# Power.net
KiCad netlist of a schematic drawn in Altium Designer
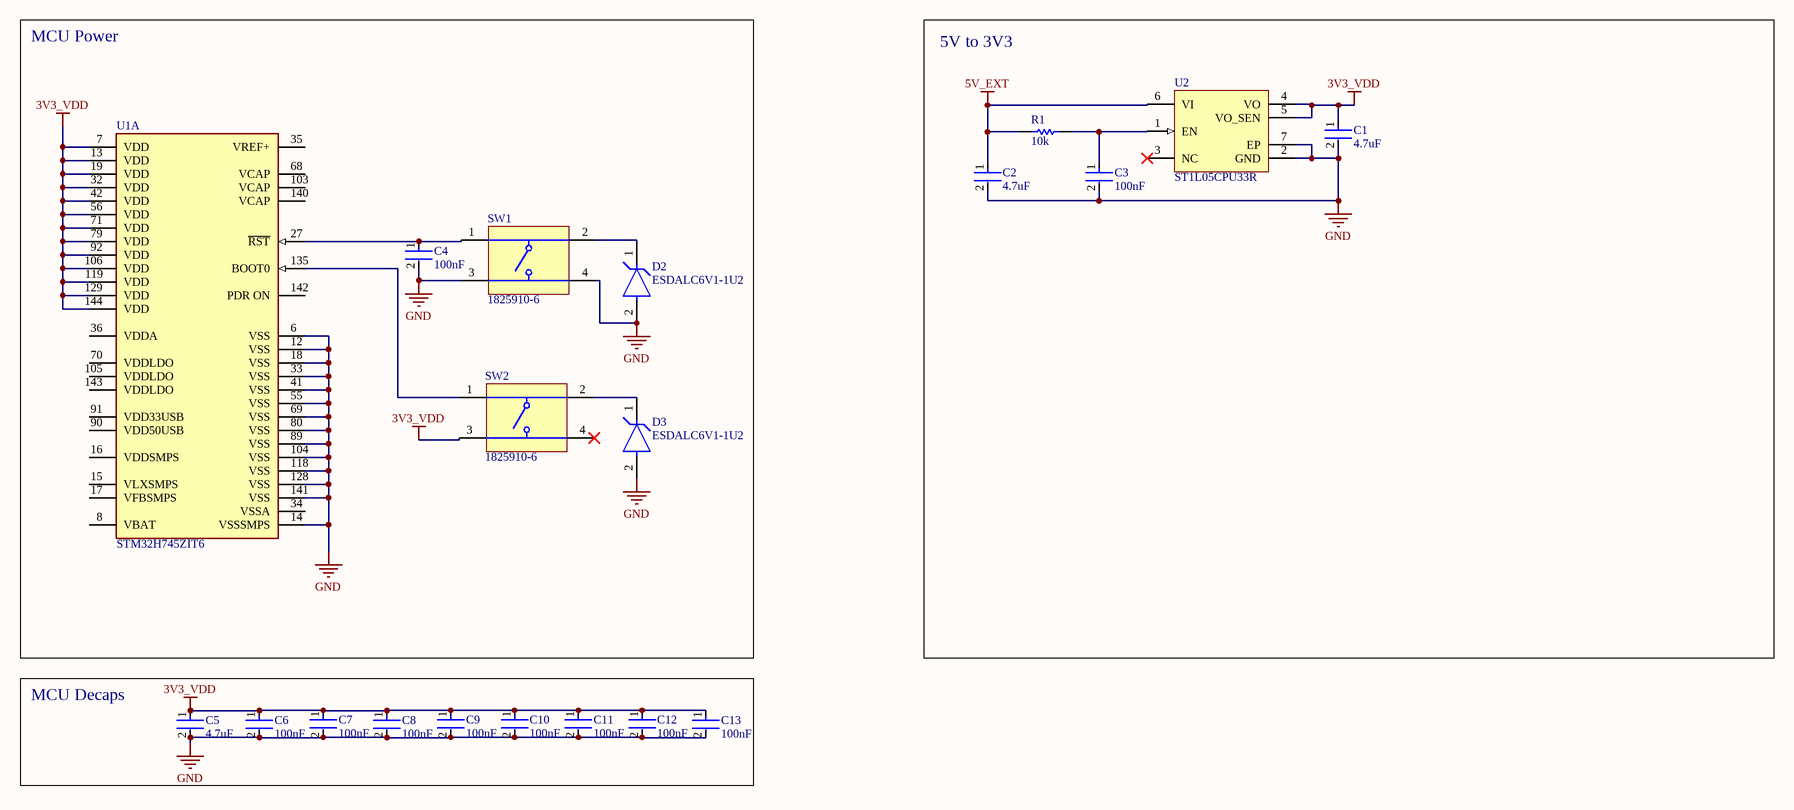
[diagram p0: Power.SchDoc]

(export (version "E")
  (design (tool "Eeschema 10.0.6"))
  (components
    (comp (ref "C1")
      (value "4.7uF")
      (footprint "FP-C0603-CG-MFG")
      (description "CAP CER 4.7UF 6.3V X5R 0603")
      (fields (field (name "TOLERANCE") "10%") (field (name "MANUFACTURER") "Kemet"))
      (libsource (lib "Altium Content Vault") (part "11868f565c42a9108669ba33697ecf6"))
    )
    (comp (ref "C2")
      (value "4.7uF")
      (footprint "FP-C0603-CG-MFG")
      (description "CAP CER 4.7UF 6.3V X5R 0603")
      (fields (field (name "TOLERANCE") "10%") (field (name "MANUFACTURER") "Kemet"))
      (libsource (lib "Altium Content Vault") (part "11868f565c42a9108669ba33697ecf6"))
    )
    (comp (ref "C3")
      (value "100nF")
      (footprint "FP-CGA3E-0_3-0_1-IPC_A")
      (description "Cap Ceramic 100nF 50V X7R 10% Pad SMD 0603 +125°C Automotive T/R")
      (fields (field (name "TOLERANCE") "10%") (field (name "VOLTAGE") "50V"))
      (libsource (lib "Altium Content Vault") (part "b4654b650e69147ec39a6b967a45e02"))
    )
    (comp (ref "C4")
      (value "100nF")
      (footprint "FP-CGA3E-0_3-0_1-IPC_A")
      (description "Cap Ceramic 100nF 50V X7R 10% Pad SMD 0603 +125°C Automotive T/R")
      (fields (field (name "TOLERANCE") "10%") (field (name "VOLTAGE") "50V"))
      (libsource (lib "Altium Content Vault") (part "b4654b650e69147ec39a6b967a45e02"))
    )
    (comp (ref "C5")
      (value "4.7uF")
      (footprint "FP-C0603-CG-MFG")
      (description "CAP CER 4.7UF 6.3V X5R 0603")
      (fields (field (name "TOLERANCE") "10%") (field (name "MANUFACTURER") "Kemet"))
      (libsource (lib "Altium Content Vault") (part "11868f565c42a9108669ba33697ecf6"))
    )
    (comp (ref "C6")
      (value "100nF")
      (footprint "FP-CGA3E-0_3-0_1-IPC_A")
      (description "Cap Ceramic 100nF 50V X7R 10% Pad SMD 0603 +125°C Automotive T/R")
      (fields (field (name "TOLERANCE") "10%") (field (name "VOLTAGE") "50V"))
      (libsource (lib "Altium Content Vault") (part "b4654b650e69147ec39a6b967a45e02"))
    )
    (comp (ref "C7")
      (value "100nF")
      (footprint "FP-CGA3E-0_3-0_1-IPC_A")
      (description "Cap Ceramic 100nF 50V X7R 10% Pad SMD 0603 +125°C Automotive T/R")
      (fields (field (name "TOLERANCE") "10%") (field (name "VOLTAGE") "50V"))
      (libsource (lib "Altium Content Vault") (part "b4654b650e69147ec39a6b967a45e02"))
    )
    (comp (ref "C8")
      (value "100nF")
      (footprint "FP-CGA3E-0_3-0_1-IPC_A")
      (description "Cap Ceramic 100nF 50V X7R 10% Pad SMD 0603 +125°C Automotive T/R")
      (fields (field (name "TOLERANCE") "10%") (field (name "VOLTAGE") "50V"))
      (libsource (lib "Altium Content Vault") (part "b4654b650e69147ec39a6b967a45e02"))
    )
    (comp (ref "C9")
      (value "100nF")
      (footprint "FP-CGA3E-0_3-0_1-IPC_A")
      (description "Cap Ceramic 100nF 50V X7R 10% Pad SMD 0603 +125°C Automotive T/R")
      (fields (field (name "TOLERANCE") "10%") (field (name "VOLTAGE") "50V"))
      (libsource (lib "Altium Content Vault") (part "b4654b650e69147ec39a6b967a45e02"))
    )
    (comp (ref "C10")
      (value "100nF")
      (footprint "FP-CGA3E-0_3-0_1-IPC_A")
      (description "Cap Ceramic 100nF 50V X7R 10% Pad SMD 0603 +125°C Automotive T/R")
      (fields (field (name "TOLERANCE") "10%") (field (name "VOLTAGE") "50V"))
      (libsource (lib "Altium Content Vault") (part "b4654b650e69147ec39a6b967a45e02"))
    )
    (comp (ref "C11")
      (value "100nF")
      (footprint "FP-CGA3E-0_3-0_1-IPC_A")
      (description "Cap Ceramic 100nF 50V X7R 10% Pad SMD 0603 +125°C Automotive T/R")
      (fields (field (name "TOLERANCE") "10%") (field (name "VOLTAGE") "50V"))
      (libsource (lib "Altium Content Vault") (part "b4654b650e69147ec39a6b967a45e02"))
    )
    (comp (ref "C12")
      (value "100nF")
      (footprint "FP-CGA3E-0_3-0_1-IPC_A")
      (description "Cap Ceramic 100nF 50V X7R 10% Pad SMD 0603 +125°C Automotive T/R")
      (fields (field (name "TOLERANCE") "10%") (field (name "VOLTAGE") "50V"))
      (libsource (lib "Altium Content Vault") (part "b4654b650e69147ec39a6b967a45e02"))
    )
    (comp (ref "C13")
      (value "100nF")
      (footprint "FP-CGA3E-0_3-0_1-IPC_A")
      (description "Cap Ceramic 100nF 50V X7R 10% Pad SMD 0603 +125°C Automotive T/R")
      (fields (field (name "TOLERANCE") "10%") (field (name "VOLTAGE") "50V"))
      (libsource (lib "Altium Content Vault") (part "b4654b650e69147ec39a6b967a45e02"))
    )
    (comp (ref "D2")
      (value "ESDALC6V1-1U2")
      (footprint "FP-ST0201-MFG")
      (description "Clamp  Ipp Tvs Diode Surface Mount ST0201")
      (fields (field (name "OCTOPART") "https://octopart.com/esdalc6v1-1u2-stmicroelectronics-11912330"))
      (libsource (lib "Altium Content Vault") (part "f813f71cba58e380607f5dd3caf9714"))
    )
    (comp (ref "D3")
      (value "ESDALC6V1-1U2")
      (footprint "FP-ST0201-MFG")
      (description "Clamp  Ipp Tvs Diode Surface Mount ST0201")
      (fields (field (name "OCTOPART") "https://octopart.com/esdalc6v1-1u2-stmicroelectronics-11912330"))
      (libsource (lib "Altium Content Vault") (part "f813f71cba58e380607f5dd3caf9714"))
    )
    (comp (ref "R1")
      (value "10k")
      (footprint "RESC1609X50X30NL8T20")
      (description "Chip Resistor, 10 KOhm, +/- 1%, 100 mW, -55 to 155 degC, 0603 (1608 Metric), RoHS, Tape and Reel")
      (fields (field (name "MANUFACTURER") "Vishay Semiconductor"))
      (libsource (lib "Altium Content Vault") (part "RES-2"))
    )
    (comp (ref "SW1")
      (value "1825910-6")
      (footprint "TECO-1825910-6_V")
      (description "Tact Switch, SPST-NO, 0.05 A, -35 to 85 degC, 4-Pin THD, RoHS, Bulk")
      (fields (field (name "MANUFACTURER") "TE Connectivity"))
      (libsource (lib "Altium Content Vault") (part "SW-SPST-4_A"))
    )
    (comp (ref "SW2")
      (value "1825910-6")
      (footprint "TECO-1825910-6_V")
      (description "Tact Switch, SPST-NO, 0.05 A, -35 to 85 degC, 4-Pin THD, RoHS, Bulk")
      (fields (field (name "MANUFACTURER") "TE Connectivity"))
      (libsource (lib "Altium Content Vault") (part "SW-SPST-4_A"))
    )
    (comp (ref "U1")
      (value "STM32H745ZIT6")
      (footprint "FP-LQFP144-1A-MFG")
      (description "HIGH-PERFORMANCE AND DSP WITH DP")
      (fields
        (field (name "OCTOPART") "https://octopart.com/stm32h745zit6-stmicroelectronics-100293939")
        (field (name "MANUFACTURER") "STMicroelectronics")
      )
      (libsource (lib "Altium Content Vault") (part "f5432ce9894f79c0085309acf87c031"))
    )
    (comp (ref "U2")
      (value "ST1L05CPU33R")
      (footprint "DFN6D_N")
      (description "Very Low Quiescent BiCMOS Voltage Regulator, 3.3V, 6-Pin VFDFPN, Tape and Reel")
      (libsource (lib "Altium Content Vault") (part "PM-REG-ST1L05C-SQ7"))
    )
  )
  (nets
    (net (code "1") (name "3V3_VDD") (class "Default")
      (node (ref "C1") (pin "1") (pinfunction "1_1") (pintype "passive"))
      (node (ref "C10") (pin "1") (pinfunction "1_1") (pintype "passive"))
      (node (ref "C11") (pin "1") (pinfunction "1_1") (pintype "passive"))
      (node (ref "C12") (pin "1") (pinfunction "1_1") (pintype "passive"))
      (node (ref "C13") (pin "1") (pinfunction "1_1") (pintype "passive"))
      (node (ref "C5") (pin "1") (pinfunction "1_1") (pintype "passive"))
      (node (ref "C6") (pin "1") (pinfunction "1_1") (pintype "passive"))
      (node (ref "C7") (pin "1") (pinfunction "1_1") (pintype "passive"))
      (node (ref "C8") (pin "1") (pinfunction "1_1") (pintype "passive"))
      (node (ref "C9") (pin "1") (pinfunction "1_1") (pintype "passive"))
      (node (ref "SW2") (pin "3") (pinfunction "3_3") (pintype "passive"))
      (node (ref "U1") (pin "106") (pinfunction "VDD_106") (pintype "power_in"))
      (node (ref "U1") (pin "119") (pinfunction "VDD_119") (pintype "power_in"))
      (node (ref "U1") (pin "129") (pinfunction "VDD_129") (pintype "power_in"))
      (node (ref "U1") (pin "13") (pinfunction "VDD_13") (pintype "power_in"))
      (node (ref "U1") (pin "144") (pinfunction "VDD_144") (pintype "power_in"))
      (node (ref "U1") (pin "19") (pinfunction "VDD_19") (pintype "power_in"))
      (node (ref "U1") (pin "32") (pinfunction "VDD_32") (pintype "power_in"))
      (node (ref "U1") (pin "42") (pinfunction "VDD_42") (pintype "power_in"))
      (node (ref "U1") (pin "56") (pinfunction "VDD_56") (pintype "power_in"))
      (node (ref "U1") (pin "7") (pinfunction "VDD_7") (pintype "power_in"))
      (node (ref "U1") (pin "71") (pinfunction "VDD_71") (pintype "power_in"))
      (node (ref "U1") (pin "79") (pinfunction "VDD_79") (pintype "power_in"))
      (node (ref "U1") (pin "92") (pinfunction "VDD_92") (pintype "power_in"))
      (node (ref "U2") (pin "4") (pinfunction "VO_4") (pintype "power_in"))
      (node (ref "U2") (pin "5") (pinfunction "VO_SEN_5") (pintype "passive"))
    )
    (net (code "2") (name "5V_EXT") (class "Default")
      (node (ref "C2") (pin "1") (pinfunction "1_1") (pintype "passive"))
      (node (ref "R1") (pin "1") (pinfunction "1_1") (pintype "passive"))
      (node (ref "U2") (pin "6") (pinfunction "VI_6") (pintype "power_in"))
    )
    (net (code "3") (name "GND") (class "Default")
      (node (ref "C1") (pin "2") (pinfunction "2_2") (pintype "passive"))
      (node (ref "C10") (pin "2") (pinfunction "2_2") (pintype "passive"))
      (node (ref "C11") (pin "2") (pinfunction "2_2") (pintype "passive"))
      (node (ref "C12") (pin "2") (pinfunction "2_2") (pintype "passive"))
      (node (ref "C13") (pin "2") (pinfunction "2_2") (pintype "passive"))
      (node (ref "C2") (pin "2") (pinfunction "2_2") (pintype "passive"))
      (node (ref "C3") (pin "2") (pinfunction "2_2") (pintype "passive"))
      (node (ref "C4") (pin "2") (pinfunction "2_2") (pintype "passive"))
      (node (ref "C5") (pin "2") (pinfunction "2_2") (pintype "passive"))
      (node (ref "C6") (pin "2") (pinfunction "2_2") (pintype "passive"))
      (node (ref "C7") (pin "2") (pinfunction "2_2") (pintype "passive"))
      (node (ref "C8") (pin "2") (pinfunction "2_2") (pintype "passive"))
      (node (ref "C9") (pin "2") (pinfunction "2_2") (pintype "passive"))
      (node (ref "D2") (pin "2") (pinfunction "A_2") (pintype "passive"))
      (node (ref "D3") (pin "2") (pinfunction "A_2") (pintype "passive"))
      (node (ref "SW1") (pin "3") (pinfunction "3_3") (pintype "passive"))
      (node (ref "SW1") (pin "4") (pinfunction "4_4") (pintype "passive"))
      (node (ref "U1") (pin "104") (pinfunction "VSS_104") (pintype "power_in"))
      (node (ref "U1") (pin "118") (pinfunction "VSS_118") (pintype "power_in"))
      (node (ref "U1") (pin "12") (pinfunction "VSS_12") (pintype "power_in"))
      (node (ref "U1") (pin "128") (pinfunction "VSS_128") (pintype "power_in"))
      (node (ref "U1") (pin "14") (pinfunction "VSSSMPS_14") (pintype "power_in"))
      (node (ref "U1") (pin "141") (pinfunction "VSS_141") (pintype "power_in"))
      (node (ref "U1") (pin "18") (pinfunction "VSS_18") (pintype "power_in"))
      (node (ref "U1") (pin "33") (pinfunction "VSS_33") (pintype "power_in"))
      (node (ref "U1") (pin "41") (pinfunction "VSS_41") (pintype "power_in"))
      (node (ref "U1") (pin "55") (pinfunction "VSS_55") (pintype "power_in"))
      (node (ref "U1") (pin "6") (pinfunction "VSS_6") (pintype "power_in"))
      (node (ref "U1") (pin "69") (pinfunction "VSS_69") (pintype "power_in"))
      (node (ref "U1") (pin "80") (pinfunction "VSS_80") (pintype "power_in"))
      (node (ref "U1") (pin "89") (pinfunction "VSS_89") (pintype "power_in"))
      (node (ref "U2") (pin "2") (pinfunction "GND_2") (pintype "power_in"))
      (node (ref "U2") (pin "7") (pinfunction "EP_7") (pintype "power_in"))
    )
    (net (code "4") (name "Net-(D2-C)") (class "Default")
      (node (ref "D2") (pin "1") (pinfunction "C_1") (pintype "passive"))
      (node (ref "SW1") (pin "2") (pinfunction "2_2") (pintype "passive"))
    )
    (net (code "5") (name "Net-(D3-C)") (class "Default")
      (node (ref "D3") (pin "1") (pinfunction "C_1") (pintype "passive"))
      (node (ref "SW2") (pin "2") (pinfunction "2_2") (pintype "passive"))
    )
    (net (code "6") (name "Net-(U1A-BOOT0)") (class "Default")
      (node (ref "SW2") (pin "1") (pinfunction "1_1") (pintype "passive"))
      (node (ref "U1") (pin "135") (pinfunction "BOOT0_135") (pintype "input"))
    )
    (net (code "7") (name "Net-(U1A-~{RST})") (class "Default")
      (node (ref "C4") (pin "1") (pinfunction "1_1") (pintype "passive"))
      (node (ref "SW1") (pin "1") (pinfunction "1_1") (pintype "passive"))
      (node (ref "U1") (pin "27") (pinfunction "~{RST}_27") (pintype "input"))
    )
    (net (code "8") (name "Net-(U2-EN)") (class "Default")
      (node (ref "C3") (pin "1") (pinfunction "1_1") (pintype "passive"))
      (node (ref "R1") (pin "2") (pinfunction "2_2") (pintype "passive"))
      (node (ref "U2") (pin "1") (pinfunction "EN_1") (pintype "input"))
    )
    (net (code "9") (name "unconnected-(SW2-Pad4)") (class "Default")
      (node (ref "SW2") (pin "4") (pinfunction "4_4") (pintype "passive+no_connect"))
    )
    (net (code "10") (name "unconnected-(U1A-PDR_ON-Pad142)") (class "Default")
      (node (ref "U1") (pin "142") (pinfunction "PDR_ON_142") (pintype "passive"))
    )
    (net (code "11") (name "unconnected-(U1A-VBAT-Pad8)") (class "Default")
      (node (ref "U1") (pin "8") (pinfunction "VBAT_8") (pintype "power_in"))
    )
    (net (code "12") (name "unconnected-(U1A-VCAP-Pad68)") (class "Default")
      (node (ref "U1") (pin "68") (pinfunction "VCAP_68") (pintype "passive"))
    )
    (net (code "13") (name "unconnected-(U1A-VCAP-Pad103)") (class "Default")
      (node (ref "U1") (pin "103") (pinfunction "VCAP_103") (pintype "passive"))
    )
    (net (code "14") (name "unconnected-(U1A-VCAP-Pad140)") (class "Default")
      (node (ref "U1") (pin "140") (pinfunction "VCAP_140") (pintype "passive"))
    )
    (net (code "15") (name "unconnected-(U1A-VDD33USB-Pad91)") (class "Default")
      (node (ref "U1") (pin "91") (pinfunction "VDD33USB_91") (pintype "power_in"))
    )
    (net (code "16") (name "unconnected-(U1A-VDD50USB-Pad90)") (class "Default")
      (node (ref "U1") (pin "90") (pinfunction "VDD50USB_90") (pintype "power_in"))
    )
    (net (code "17") (name "unconnected-(U1A-VDDA-Pad36)") (class "Default")
      (node (ref "U1") (pin "36") (pinfunction "VDDA_36") (pintype "power_in"))
    )
    (net (code "18") (name "unconnected-(U1A-VDDLDO-Pad70)") (class "Default")
      (node (ref "U1") (pin "70") (pinfunction "VDDLDO_70") (pintype "power_in"))
    )
    (net (code "19") (name "unconnected-(U1A-VDDLDO-Pad105)") (class "Default")
      (node (ref "U1") (pin "105") (pinfunction "VDDLDO_105") (pintype "power_in"))
    )
    (net (code "20") (name "unconnected-(U1A-VDDLDO-Pad143)") (class "Default")
      (node (ref "U1") (pin "143") (pinfunction "VDDLDO_143") (pintype "power_in"))
    )
    (net (code "21") (name "unconnected-(U1A-VDDSMPS-Pad16)") (class "Default")
      (node (ref "U1") (pin "16") (pinfunction "VDDSMPS_16") (pintype "power_in"))
    )
    (net (code "22") (name "unconnected-(U1A-VFBSMPS-Pad17)") (class "Default")
      (node (ref "U1") (pin "17") (pinfunction "VFBSMPS_17") (pintype "power_in"))
    )
    (net (code "23") (name "unconnected-(U1A-VLXSMPS-Pad15)") (class "Default")
      (node (ref "U1") (pin "15") (pinfunction "VLXSMPS_15") (pintype "power_in"))
    )
    (net (code "24") (name "unconnected-(U1A-VREF+-Pad35)") (class "Default")
      (node (ref "U1") (pin "35") (pinfunction "VREF+_35") (pintype "power_in"))
    )
    (net (code "25") (name "unconnected-(U1A-VSSA-Pad34)") (class "Default")
      (node (ref "U1") (pin "34") (pinfunction "VSSA_34") (pintype "power_in"))
    )
    (net (code "26") (name "unconnected-(U2-NC-Pad3)") (class "Default")
      (node (ref "U2") (pin "3") (pinfunction "NC_3") (pintype "passive+no_connect"))
    )
  )
)
